# OSO-SWAT-A1-0x.net
KiCad netlist of a schematic drawn in EAGLE
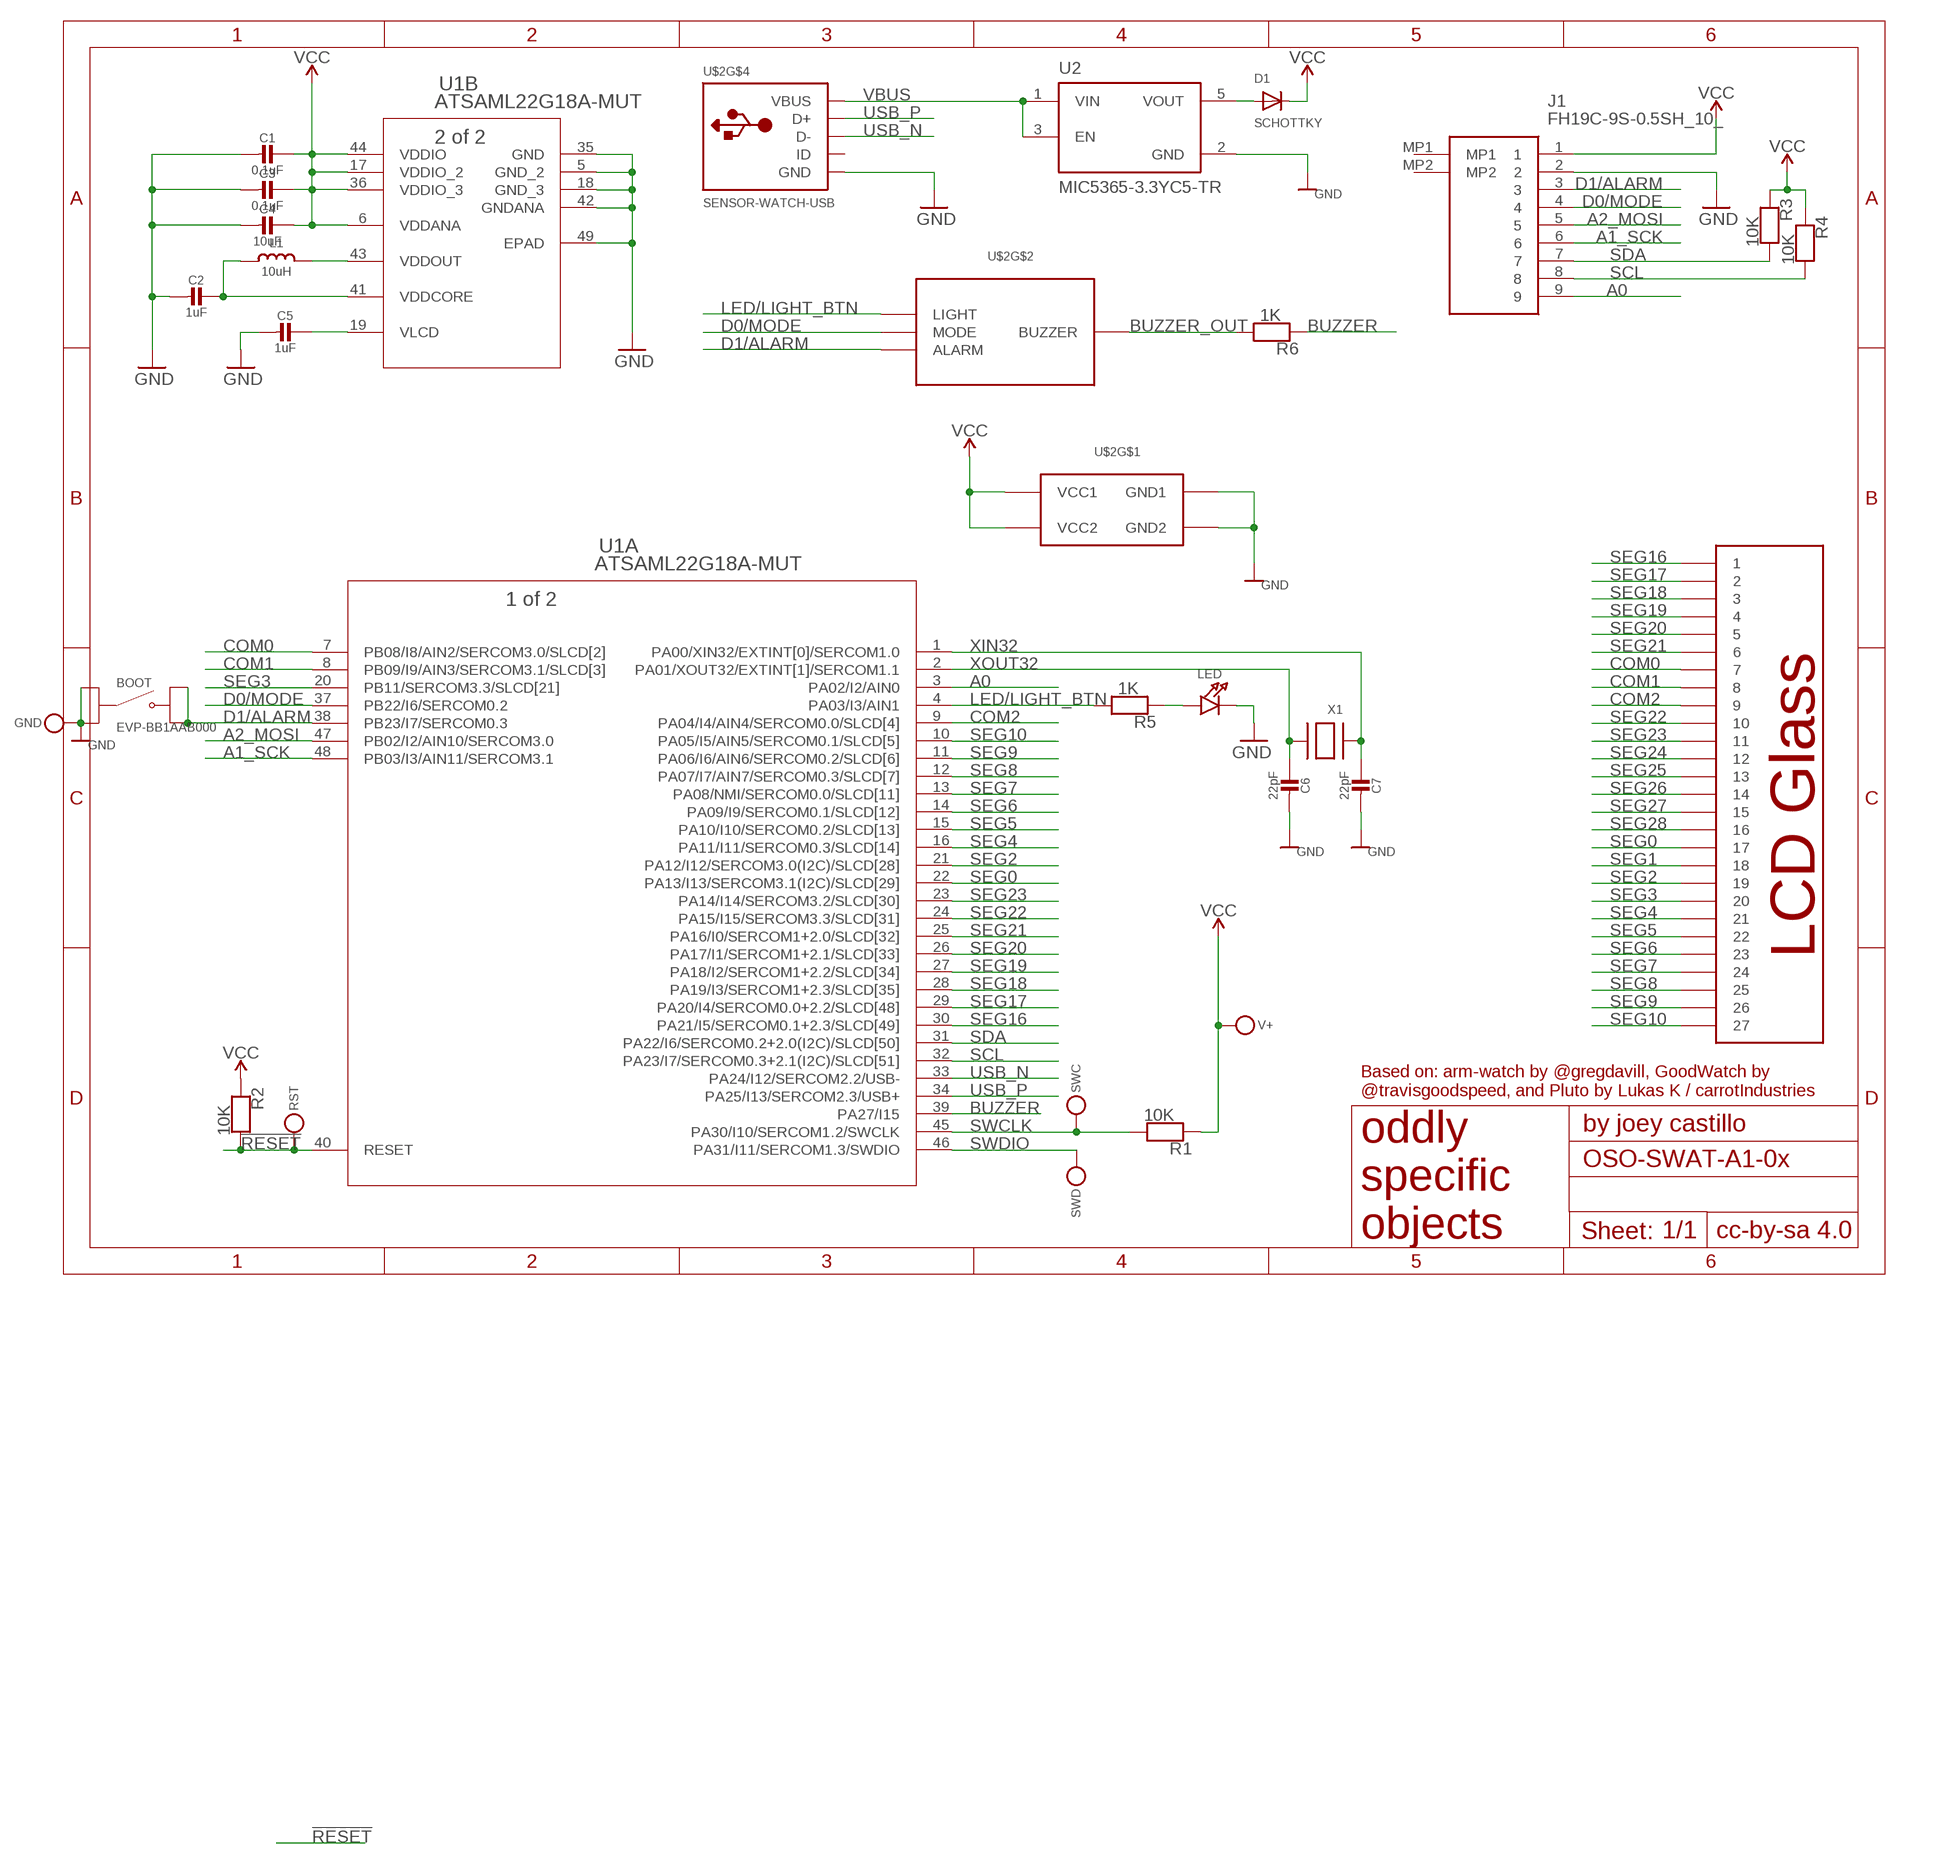
[diagram p0: schematic, sheet 1]

(export (version "E")
  (design (tool "Eeschema 10.0.6"))
  (components
    (comp (ref "BOOT")
      (value "EVP-BB1AAB000")
      (footprint "eagle-import:SW_EVP-BB1AAB000")
      (fields
        (field (name "DIGI-KEY_PART_NUMBER") "P124390CT-ND")
        (field (name "MF") "Panasonic Electronic Components")
      )
      (libsource (lib "eagle-import") (part "EVP-BB1AAB000"))
    )
    (comp (ref "C1")
      (value "0.1uF")
      (footprint "eagle-import:_0603MP")
      (libsource (lib "eagle-import") (part "CAP_CERAMIC_0603MP"))
    )
    (comp (ref "C2")
      (value "1uF")
      (footprint "eagle-import:_0603MP")
      (libsource (lib "eagle-import") (part "CAP_CERAMIC_0603MP"))
    )
    (comp (ref "C3")
      (value "0.1uF")
      (footprint "eagle-import:_0603MP")
      (libsource (lib "eagle-import") (part "CAP_CERAMIC_0603MP"))
    )
    (comp (ref "C4")
      (value "10uF")
      (footprint "eagle-import:_0603MP")
      (libsource (lib "eagle-import") (part "CAP_CERAMIC_0603MP"))
    )
    (comp (ref "C5")
      (value "1uF")
      (footprint "eagle-import:_0603MP")
      (libsource (lib "eagle-import") (part "CAP_CERAMIC_0603MP"))
    )
    (comp (ref "C6")
      (value "22pF")
      (footprint "eagle-import:_0603MP")
      (libsource (lib "eagle-import") (part "CAP_CERAMIC_0603MP"))
    )
    (comp (ref "C7")
      (value "22pF")
      (footprint "eagle-import:_0603MP")
      (libsource (lib "eagle-import") (part "CAP_CERAMIC_0603MP"))
    )
    (comp (ref "D1")
      (value "SCHOTTKY")
      (footprint "eagle-import:SOD-323F")
      (libsource (lib "eagle-import") (part "DIODESOD-323F"))
    )
    (comp (ref "GND")
      (value "MICROBUILDER_TESTPOINTPAD1MM")
      (footprint "eagle-import:MICROBUILDER_TESTPOINT_PAD_1MM")
      (libsource (lib "eagle-import") (part "MICROBUILDER_TESTPOINTPAD1MM"))
    )
    (comp (ref "J1")
      (value "FH19C-9S-0.5SH_10_")
      (footprint "eagle-import:FH19C9S05SH10")
      (fields
        (field (name "MANUFACTURER_PART_NUMBER") "FH19C-9S-0.5SH(10)")
        (field (name "MOUSER_PART_NUMBER") "798-FH19C9S05SH10")
      )
      (libsource (lib "eagle-import") (part "FH19C-9S-0.5SH_10_"))
    )
    (comp (ref "L1")
      (value "10uH")
      (footprint "eagle-import:MICROBUILDER__0805MP")
      (libsource (lib "eagle-import") (part "MICROBUILDER_INDUCTOR_0805MP"))
    )
    (comp (ref "LED")
      (value "LED0805_NOOUTLINE")
      (footprint "eagle-import:CHIPLED_0805_NOOUTLINE")
      (libsource (lib "eagle-import") (part "LED0805_NOOUTLINE"))
    )
    (comp (ref "R1")
      (value "10K")
      (footprint "eagle-import:_0603MP")
      (libsource (lib "eagle-import") (part "RESISTOR_0603MP"))
    )
    (comp (ref "R2")
      (value "10K")
      (footprint "eagle-import:_0402MP")
      (libsource (lib "eagle-import") (part "RESISTOR_0402MP"))
    )
    (comp (ref "R3")
      (value "10K")
      (footprint "eagle-import:_0603MP")
      (libsource (lib "eagle-import") (part "RESISTOR_0603MP"))
    )
    (comp (ref "R4")
      (value "10K")
      (footprint "eagle-import:_0603MP")
      (libsource (lib "eagle-import") (part "RESISTOR_0603MP"))
    )
    (comp (ref "R5")
      (value "1K")
      (footprint "eagle-import:_0603MP")
      (libsource (lib "eagle-import") (part "RESISTOR_0603MP"))
    )
    (comp (ref "R6")
      (value "1K")
      (footprint "eagle-import:_0603MP")
      (libsource (lib "eagle-import") (part "RESISTOR_0603MP"))
    )
    (comp (ref "RST")
      (value "MICROBUILDER_TESTPOINTPAD1MM")
      (footprint "eagle-import:MICROBUILDER_TESTPOINT_PAD_1MM")
      (libsource (lib "eagle-import") (part "MICROBUILDER_TESTPOINTPAD1MM"))
    )
    (comp (ref "SWC")
      (value "MICROBUILDER_TESTPOINTPAD1MM")
      (footprint "eagle-import:MICROBUILDER_TESTPOINT_PAD_1MM")
      (libsource (lib "eagle-import") (part "MICROBUILDER_TESTPOINTPAD1MM"))
    )
    (comp (ref "SWD")
      (value "MICROBUILDER_TESTPOINTPAD1MM")
      (footprint "eagle-import:MICROBUILDER_TESTPOINT_PAD_1MM")
      (libsource (lib "eagle-import") (part "MICROBUILDER_TESTPOINTPAD1MM"))
    )
    (comp (ref "U$2")
      (value "SENSOR-WATCH-USB")
      (footprint "eagle-import:CASIO-F91W-OUTLINE-USB")
      (libsource (lib "eagle-import") (part "SENSOR-WATCH-USB"))
    )
    (comp (ref "U1")
      (value "ATSAML22G18A-MUT")
      (footprint "eagle-import:QFN48_7X7MC_MCH")
      (fields (field (name "COPYRIGHT") "Copyright (C) 2018 Accelerated Designs. All rights reserved"))
      (libsource (lib "eagle-import") (part "ATSAML22G18A-MUT"))
    )
    (comp (ref "U2")
      (value "MIC5365-3.3YC5-TR")
      (footprint "eagle-import:SOT65P210X110-5N")
      (fields (field (name "DIGI-KEY_PART_NUMBER") "576-3193-1-ND") (field (name "MF") "Microchip"))
      (libsource (lib "eagle-import") (part "MIC5365-3.3YC5-TR"))
    )
    (comp (ref "V+")
      (value "MICROBUILDER_TESTPOINTPAD1MM")
      (footprint "eagle-import:MICROBUILDER_TESTPOINT_PAD_1MM")
      (libsource (lib "eagle-import") (part "MICROBUILDER_TESTPOINTPAD1MM"))
    )
    (comp (ref "X1")
      (value "XTAL-3.2X1.5")
      (footprint "eagle-import:XTAL3215")
      (libsource (lib "eagle-import") (part "XTAL-3.2X1.5"))
    )
  )
  (nets
    (net (code "1") (name "/A0") (class "Default")
      (node (ref "J1") (pin "9") (pinfunction "9_9") (pintype "bidirectional"))
      (node (ref "U1") (pin "3") (pinfunction "PA02/I2/AIN0_3") (pintype "bidirectional"))
    )
    (net (code "2") (name "/A1_SCK") (class "Default")
      (node (ref "J1") (pin "6") (pinfunction "6_6") (pintype "bidirectional"))
      (node (ref "U1") (pin "48") (pinfunction "PB03/I3/AIN11/SERCOM3.1_48") (pintype "bidirectional"))
    )
    (net (code "3") (name "/A2_MOSI") (class "Default")
      (node (ref "J1") (pin "5") (pinfunction "5_5") (pintype "bidirectional"))
      (node (ref "U1") (pin "47") (pinfunction "PB02/I2/AIN10/SERCOM3.0_47") (pintype "bidirectional"))
    )
    (net (code "4") (name "/BUZZER") (class "Default")
      (node (ref "R6") (pin "1") (pinfunction "1_1") (pintype "passive"))
      (node (ref "U1") (pin "39") (pinfunction "PA27/I15_39") (pintype "bidirectional"))
    )
    (net (code "5") (name "/BUZZER_OUT") (class "Default")
      (node (ref "R6") (pin "2") (pinfunction "2_2") (pintype "passive"))
      (node (ref "U$2") (pin "BUZZER") (pinfunction "BUZZER_BUZZER") (pintype "bidirectional"))
    )
    (net (code "6") (name "/COM0") (class "Default")
      (node (ref "U$2") (pin "7") (pinfunction "7_7") (pintype "input"))
      (node (ref "U1") (pin "7") (pinfunction "PB08/I8/AIN2/SERCOM3.0/SLCD[2]_7") (pintype "bidirectional"))
    )
    (net (code "7") (name "/COM1") (class "Default")
      (node (ref "U$2") (pin "8") (pinfunction "8_8") (pintype "input"))
      (node (ref "U1") (pin "8") (pinfunction "PB09/I9/AIN3/SERCOM3.1/SLCD[3]_8") (pintype "bidirectional"))
    )
    (net (code "8") (name "/COM2") (class "Default")
      (node (ref "U$2") (pin "9") (pinfunction "9_9") (pintype "input"))
      (node (ref "U1") (pin "9") (pinfunction "PA04/I4/AIN4/SERCOM0.0/SLCD[4]_9") (pintype "bidirectional"))
    )
    (net (code "9") (name "/D0{slash}MODE") (class "Default")
      (node (ref "J1") (pin "4") (pinfunction "4_4") (pintype "bidirectional"))
      (node (ref "U$2") (pin "MODE") (pinfunction "MODE_MODE") (pintype "bidirectional"))
      (node (ref "U1") (pin "37") (pinfunction "PB22/I6/SERCOM0.2_37") (pintype "bidirectional"))
    )
    (net (code "10") (name "/D1{slash}ALARM") (class "Default")
      (node (ref "BOOT") (pin "B1") (pinfunction "B1_B1") (pintype "passive"))
      (node (ref "BOOT") (pin "B2") (pinfunction "B2_B2") (pintype "passive"))
      (node (ref "J1") (pin "3") (pinfunction "3_3") (pintype "bidirectional"))
      (node (ref "U$2") (pin "ALARM") (pinfunction "ALARM_ALARM") (pintype "bidirectional"))
      (node (ref "U1") (pin "38") (pinfunction "PB23/I7/SERCOM0.3_38") (pintype "bidirectional"))
    )
    (net (code "11") (name "/LED{slash}LIGHT_BTN") (class "Default")
      (node (ref "R5") (pin "2") (pinfunction "2_2") (pintype "passive"))
      (node (ref "U$2") (pin "LIGHT") (pinfunction "LIGHT_LIGHT") (pintype "bidirectional"))
      (node (ref "U1") (pin "4") (pinfunction "PA03/I3/AIN1_4") (pintype "bidirectional"))
    )
    (net (code "12") (name "/SCL") (class "Default")
      (node (ref "J1") (pin "8") (pinfunction "8_8") (pintype "bidirectional"))
      (node (ref "R4") (pin "2") (pinfunction "2_2") (pintype "passive"))
      (node (ref "U1") (pin "32") (pinfunction "PA23/I7/SERCOM0.3+2.1(I2C)/SLCD[51]_32") (pintype "bidirectional"))
    )
    (net (code "13") (name "/SDA") (class "Default")
      (node (ref "J1") (pin "7") (pinfunction "7_7") (pintype "bidirectional"))
      (node (ref "R3") (pin "2") (pinfunction "2_2") (pintype "passive"))
      (node (ref "U1") (pin "31") (pinfunction "PA22/I6/SERCOM0.2+2.0(I2C)/SLCD[50]_31") (pintype "bidirectional"))
    )
    (net (code "14") (name "/SEG0") (class "Default")
      (node (ref "U$2") (pin "17") (pinfunction "17_17") (pintype "input"))
      (node (ref "U1") (pin "22") (pinfunction "PA13/I13/SERCOM3.1(I2C)/SLCD[29]_22") (pintype "bidirectional"))
    )
    (net (code "15") (name "/SEG1") (class "Default")
      (node (ref "U$2") (pin "18") (pinfunction "18_18") (pintype "input"))
    )
    (net (code "16") (name "/SEG2") (class "Default")
      (node (ref "U$2") (pin "19") (pinfunction "19_19") (pintype "input"))
      (node (ref "U1") (pin "21") (pinfunction "PA12/I12/SERCOM3.0(I2C)/SLCD[28]_21") (pintype "bidirectional"))
    )
    (net (code "17") (name "/SEG3") (class "Default")
      (node (ref "U$2") (pin "20") (pinfunction "20_20") (pintype "input"))
      (node (ref "U1") (pin "20") (pinfunction "PB11/SERCOM3.3/SLCD[21]_20") (pintype "bidirectional"))
    )
    (net (code "18") (name "/SEG4") (class "Default")
      (node (ref "U$2") (pin "21") (pinfunction "21_21") (pintype "input"))
      (node (ref "U1") (pin "16") (pinfunction "PA11/I11/SERCOM0.3/SLCD[14]_16") (pintype "bidirectional"))
    )
    (net (code "19") (name "/SEG5") (class "Default")
      (node (ref "U$2") (pin "22") (pinfunction "22_22") (pintype "input"))
      (node (ref "U1") (pin "15") (pinfunction "PA10/I10/SERCOM0.2/SLCD[13]_15") (pintype "bidirectional"))
    )
    (net (code "20") (name "/SEG6") (class "Default")
      (node (ref "U$2") (pin "23") (pinfunction "23_23") (pintype "input"))
      (node (ref "U1") (pin "14") (pinfunction "PA09/I9/SERCOM0.1/SLCD[12]_14") (pintype "bidirectional"))
    )
    (net (code "21") (name "/SEG7") (class "Default")
      (node (ref "U$2") (pin "24") (pinfunction "24_24") (pintype "input"))
      (node (ref "U1") (pin "13") (pinfunction "PA08/NMI/SERCOM0.0/SLCD[11]_13") (pintype "bidirectional"))
    )
    (net (code "22") (name "/SEG8") (class "Default")
      (node (ref "U$2") (pin "25") (pinfunction "25_25") (pintype "input"))
      (node (ref "U1") (pin "12") (pinfunction "PA07/I7/AIN7/SERCOM0.3/SLCD[7]_12") (pintype "bidirectional"))
    )
    (net (code "23") (name "/SEG9") (class "Default")
      (node (ref "U$2") (pin "26") (pinfunction "26_26") (pintype "input"))
      (node (ref "U1") (pin "11") (pinfunction "PA06/I6/AIN6/SERCOM0.2/SLCD[6]_11") (pintype "bidirectional"))
    )
    (net (code "24") (name "/SEG10") (class "Default")
      (node (ref "U$2") (pin "27") (pinfunction "27_27") (pintype "input"))
      (node (ref "U1") (pin "10") (pinfunction "PA05/I5/AIN5/SERCOM0.1/SLCD[5]_10") (pintype "bidirectional"))
    )
    (net (code "25") (name "/SEG16") (class "Default")
      (node (ref "U$2") (pin "1") (pinfunction "1_1") (pintype "input"))
      (node (ref "U1") (pin "30") (pinfunction "PA21/I5/SERCOM0.1+2.3/SLCD[49]_30") (pintype "bidirectional"))
    )
    (net (code "26") (name "/SEG17") (class "Default")
      (node (ref "U$2") (pin "2") (pinfunction "2_2") (pintype "input"))
      (node (ref "U1") (pin "29") (pinfunction "PA20/I4/SERCOM0.0+2.2/SLCD[48]_29") (pintype "bidirectional"))
    )
    (net (code "27") (name "/SEG18") (class "Default")
      (node (ref "U$2") (pin "3") (pinfunction "3_3") (pintype "input"))
      (node (ref "U1") (pin "28") (pinfunction "PA19/I3/SERCOM1+2.3/SLCD[35]_28") (pintype "bidirectional"))
    )
    (net (code "28") (name "/SEG19") (class "Default")
      (node (ref "U$2") (pin "4") (pinfunction "4_4") (pintype "input"))
      (node (ref "U1") (pin "27") (pinfunction "PA18/I2/SERCOM1+2.2/SLCD[34]_27") (pintype "bidirectional"))
    )
    (net (code "29") (name "/SEG20") (class "Default")
      (node (ref "U$2") (pin "5") (pinfunction "5_5") (pintype "input"))
      (node (ref "U1") (pin "26") (pinfunction "PA17/I1/SERCOM1+2.1/SLCD[33]_26") (pintype "bidirectional"))
    )
    (net (code "30") (name "/SEG21") (class "Default")
      (node (ref "U$2") (pin "6") (pinfunction "6_6") (pintype "input"))
      (node (ref "U1") (pin "25") (pinfunction "PA16/I0/SERCOM1+2.0/SLCD[32]_25") (pintype "bidirectional"))
    )
    (net (code "31") (name "/SEG22") (class "Default")
      (node (ref "U$2") (pin "10") (pinfunction "10_10") (pintype "input"))
      (node (ref "U1") (pin "24") (pinfunction "PA15/I15/SERCOM3.3/SLCD[31]_24") (pintype "bidirectional"))
    )
    (net (code "32") (name "/SEG23") (class "Default")
      (node (ref "U$2") (pin "11") (pinfunction "11_11") (pintype "input"))
      (node (ref "U1") (pin "23") (pinfunction "PA14/I14/SERCOM3.2/SLCD[30]_23") (pintype "bidirectional"))
    )
    (net (code "33") (name "/SEG24") (class "Default")
      (node (ref "U$2") (pin "12") (pinfunction "12_12") (pintype "input"))
    )
    (net (code "34") (name "/SEG25") (class "Default")
      (node (ref "U$2") (pin "13") (pinfunction "13_13") (pintype "input"))
    )
    (net (code "35") (name "/SEG26") (class "Default")
      (node (ref "U$2") (pin "14") (pinfunction "14_14") (pintype "input"))
    )
    (net (code "36") (name "/SEG27") (class "Default")
      (node (ref "U$2") (pin "15") (pinfunction "15_15") (pintype "input"))
    )
    (net (code "37") (name "/SEG28") (class "Default")
      (node (ref "U$2") (pin "16") (pinfunction "16_16") (pintype "input"))
    )
    (net (code "38") (name "/SWCLK") (class "Default")
      (node (ref "R1") (pin "2") (pinfunction "2_2") (pintype "passive"))
      (node (ref "SWC") (pin "P$1") (pinfunction "P$1_P$1") (pintype "bidirectional"))
      (node (ref "U1") (pin "45") (pinfunction "PA30/I10/SERCOM1.2/SWCLK_45") (pintype "bidirectional"))
    )
    (net (code "39") (name "/SWDIO") (class "Default")
      (node (ref "SWD") (pin "P$1") (pinfunction "P$1_P$1") (pintype "bidirectional"))
      (node (ref "U1") (pin "46") (pinfunction "PA31/I11/SERCOM1.3/SWDIO_46") (pintype "bidirectional"))
    )
    (net (code "40") (name "/USB_N") (class "Default")
      (node (ref "U$2") (pin "USB_N") (pinfunction "D-_USB_N") (pintype "bidirectional"))
      (node (ref "U1") (pin "33") (pinfunction "PA24/I12/SERCOM2.2/USB-_33") (pintype "bidirectional"))
    )
    (net (code "41") (name "/USB_P") (class "Default")
      (node (ref "U$2") (pin "USB_P") (pinfunction "D+_USB_P") (pintype "bidirectional"))
      (node (ref "U1") (pin "34") (pinfunction "PA25/I13/SERCOM2.3/USB+_34") (pintype "bidirectional"))
    )
    (net (code "42") (name "/VBUS") (class "Default")
      (node (ref "U$2") (pin "VBUS") (pinfunction "VBUS_VBUS") (pintype "power_in"))
      (node (ref "U2") (pin "1") (pinfunction "VIN_1") (pintype "input"))
      (node (ref "U2") (pin "3") (pinfunction "EN_3") (pintype "input"))
    )
    (net (code "43") (name "/XIN32") (class "Default")
      (node (ref "C7") (pin "1") (pinfunction "1_1") (pintype "passive"))
      (node (ref "U1") (pin "1") (pinfunction "PA00/XIN32/EXTINT[0]/SERCOM1.0_1") (pintype "bidirectional"))
      (node (ref "X1") (pin "P$1") (pinfunction "P$1_P$1") (pintype "bidirectional"))
    )
    (net (code "44") (name "/XOUT32") (class "Default")
      (node (ref "C6") (pin "1") (pinfunction "1_1") (pintype "passive"))
      (node (ref "U1") (pin "2") (pinfunction "PA01/XOUT32/EXTINT[1]/SERCOM1.1_2") (pintype "bidirectional"))
      (node (ref "X1") (pin "P$2") (pinfunction "P$2_P$2") (pintype "bidirectional"))
    )
    (net (code "45") (name "/~{RESET}") (class "Default")
      (node (ref "R2") (pin "2") (pinfunction "2_2") (pintype "passive"))
      (node (ref "RST") (pin "P$1") (pinfunction "P$1_P$1") (pintype "bidirectional"))
      (node (ref "U1") (pin "40") (pinfunction "RESET_40") (pintype "passive"))
    )
    (net (code "46") (name "GND") (class "Default")
      (node (ref "BOOT") (pin "A1") (pinfunction "A1_A1") (pintype "passive"))
      (node (ref "BOOT") (pin "A2") (pinfunction "A2_A2") (pintype "passive"))
      (node (ref "C1") (pin "2") (pinfunction "2_2") (pintype "passive"))
      (node (ref "C2") (pin "2") (pinfunction "2_2") (pintype "passive"))
      (node (ref "C3") (pin "2") (pinfunction "2_2") (pintype "passive"))
      (node (ref "C4") (pin "2") (pinfunction "2_2") (pintype "passive"))
      (node (ref "C5") (pin "2") (pinfunction "2_2") (pintype "passive"))
      (node (ref "C6") (pin "2") (pinfunction "2_2") (pintype "passive"))
      (node (ref "C7") (pin "2") (pinfunction "2_2") (pintype "passive"))
      (node (ref "GND") (pin "P$1") (pinfunction "P$1_P$1") (pintype "bidirectional"))
      (node (ref "J1") (pin "2") (pinfunction "2_2") (pintype "bidirectional"))
      (node (ref "LED") (pin "C") (pinfunction "C_C") (pintype "passive"))
      (node (ref "U$2") (pin "GND") (pinfunction "GND_GND") (pintype "power_in"))
      (node (ref "U$2") (pin "GND1") (pinfunction "GND1_GND1") (pintype "bidirectional"))
      (node (ref "U$2") (pin "GND2") (pinfunction "GND2_GND2") (pintype "bidirectional"))
      (node (ref "U1") (pin "18") (pinfunction "GND_3_18") (pintype "passive"))
      (node (ref "U1") (pin "35") (pinfunction "GND_35") (pintype "passive"))
      (node (ref "U1") (pin "42") (pinfunction "GNDANA_42") (pintype "passive"))
      (node (ref "U1") (pin "49") (pinfunction "EPAD_49") (pintype "passive"))
      (node (ref "U1") (pin "5") (pinfunction "GND_2_5") (pintype "passive"))
      (node (ref "U2") (pin "2") (pinfunction "GND_2") (pintype "power_in"))
    )
    (net (code "47") (name "Net-(LED-PadA)") (class "Default")
      (node (ref "LED") (pin "A") (pinfunction "A_A") (pintype "passive"))
      (node (ref "R5") (pin "1") (pinfunction "1_1") (pintype "passive"))
    )
    (net (code "48") (name "Net-(U1B-VDDCORE)") (class "Default")
      (node (ref "C2") (pin "1") (pinfunction "1_1") (pintype "passive"))
      (node (ref "L1") (pin "1") (pinfunction "1_1") (pintype "passive"))
      (node (ref "U1") (pin "41") (pinfunction "VDDCORE_41") (pintype "power_in"))
    )
    (net (code "49") (name "Net-(U1B-VDDOUT)") (class "Default")
      (node (ref "L1") (pin "2") (pinfunction "2_2") (pintype "passive"))
      (node (ref "U1") (pin "43") (pinfunction "VDDOUT_43") (pintype "output"))
    )
    (net (code "50") (name "Net-(U1B-VLCD)") (class "Default")
      (node (ref "C5") (pin "1") (pinfunction "1_1") (pintype "passive"))
      (node (ref "U1") (pin "19") (pinfunction "VLCD_19") (pintype "passive"))
    )
    (net (code "51") (name "Net-(U2-VOUT)") (class "Default")
      (node (ref "D1") (pin "A") (pinfunction "A_A") (pintype "passive"))
      (node (ref "U2") (pin "5") (pinfunction "VOUT_5") (pintype "output"))
    )
    (net (code "52") (name "VCC") (class "Default")
      (node (ref "C1") (pin "1") (pinfunction "1_1") (pintype "passive"))
      (node (ref "C3") (pin "1") (pinfunction "1_1") (pintype "passive"))
      (node (ref "C4") (pin "1") (pinfunction "1_1") (pintype "passive"))
      (node (ref "D1") (pin "C") (pinfunction "C_C") (pintype "passive"))
      (node (ref "J1") (pin "1") (pinfunction "1_1") (pintype "bidirectional"))
      (node (ref "R1") (pin "1") (pinfunction "1_1") (pintype "passive"))
      (node (ref "R2") (pin "1") (pinfunction "1_1") (pintype "passive"))
      (node (ref "R3") (pin "1") (pinfunction "1_1") (pintype "passive"))
      (node (ref "R4") (pin "1") (pinfunction "1_1") (pintype "passive"))
      (node (ref "U$2") (pin "VCC1") (pinfunction "VCC1_VCC1") (pintype "bidirectional"))
      (node (ref "U$2") (pin "VCC2") (pinfunction "VCC2_VCC2") (pintype "bidirectional"))
      (node (ref "U1") (pin "17") (pinfunction "VDDIO_2_17") (pintype "power_in"))
      (node (ref "U1") (pin "36") (pinfunction "VDDIO_3_36") (pintype "power_in"))
      (node (ref "U1") (pin "44") (pinfunction "VDDIO_44") (pintype "power_in"))
      (node (ref "U1") (pin "6") (pinfunction "VDDANA_6") (pintype "power_in"))
      (node (ref "V+") (pin "P$1") (pinfunction "P$1_P$1") (pintype "bidirectional"))
    )
    (net (code "53") (name "unconnected-(J1-PadMP1)") (class "Default")
      (node (ref "J1") (pin "MP1") (pinfunction "MP1_MP1") (pintype "bidirectional"))
    )
    (net (code "54") (name "unconnected-(J1-PadMP2)") (class "Default")
      (node (ref "J1") (pin "MP2") (pinfunction "MP2_MP2") (pintype "bidirectional"))
    )
    (net (code "55") (name "unconnected-(U$2D-ID-PadUSB_ID)") (class "Default")
      (node (ref "U$2") (pin "USB_ID") (pinfunction "ID_USB_ID") (pintype "bidirectional"))
    )
  )
)
